# Cansat2019_3279_Container_v04.net
KiCad netlist of a schematic drawn in EAGLE
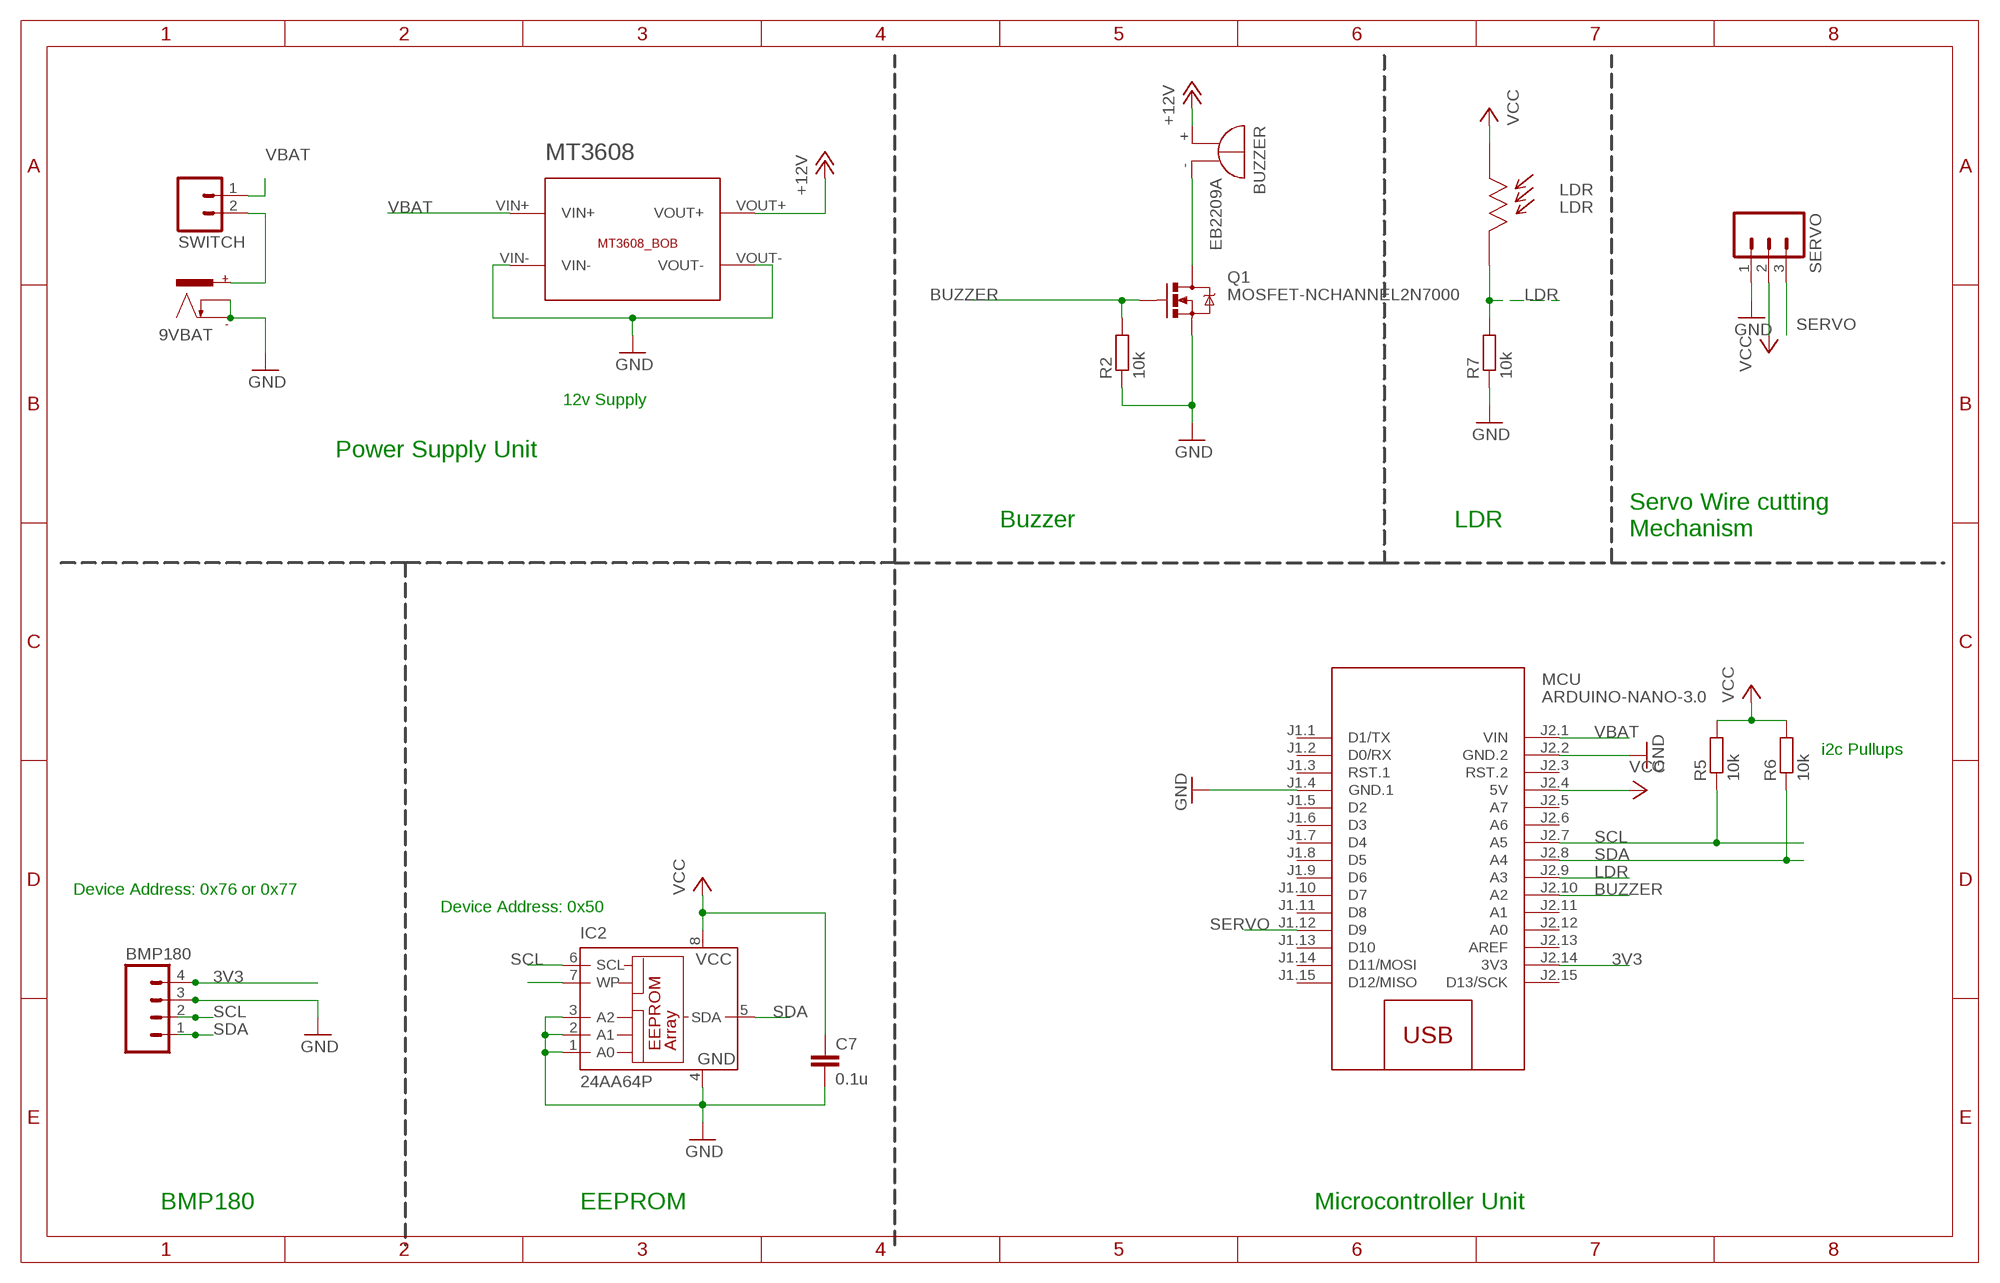
[diagram p0: schematic, sheet 1]

(export (version "E")
  (design (tool "Eeschema 10.0.6"))
  (components
    (comp (ref "9VBAT")
      (value "POWER_CON")
      (footprint "eagle-import:NEB21R")
      (libsource (lib "eagle-import") (part "POWER_CON"))
    )
    (comp (ref "BMP180")
      (value "M04")
      (footprint "eagle-import:04P")
      (libsource (lib "eagle-import") (part "M04"))
    )
    (comp (ref "BUZZER")
      (value "EB2209A")
      (footprint "eagle-import:EB2209A")
      (libsource (lib "eagle-import") (part "EB2209A"))
    )
    (comp (ref "C7")
      (value "0.1u")
      (footprint "eagle-import:C025-025X050")
      (libsource (lib "eagle-import") (part "C-EU025-025X050"))
    )
    (comp (ref "IC2")
      (value "24AA64P")
      (footprint "eagle-import:DIL8")
      (fields (field (name "MF") "MICROCHIP") (field (name "MPN") "24AA64-I/P"))
      (libsource (lib "eagle-import") (part "24PAA64"))
    )
    (comp (ref "LDR")
      (value "LDR")
      (footprint "eagle-import:LDR-5MM")
      (libsource (lib "eagle-import") (part "LDR"))
    )
    (comp (ref "MCU")
      (value "ARDUINO-NANO-3.0")
      (footprint "eagle-import:ARDUINO-NANO-3.0")
      (libsource (lib "eagle-import") (part "ARDUINO-NANO-3.0"))
    )
    (comp (ref "MT3608")
      (value "MT3608_BOB")
      (footprint "eagle-import:MT3608_BOB")
      (libsource (lib "eagle-import") (part "MT3608_BOB"))
    )
    (comp (ref "Q1")
      (value "MOSFET-NCHANNEL2N7000")
      (footprint "eagle-import:TO-92")
      (libsource (lib "eagle-import") (part "MOSFET-NCHANNEL2N7000"))
    )
    (comp (ref "R2")
      (value "10k")
      (footprint "eagle-import:0204_7")
      (libsource (lib "eagle-import") (part "R-EU_0204/7"))
    )
    (comp (ref "R5")
      (value "10k")
      (footprint "eagle-import:0204_7")
      (libsource (lib "eagle-import") (part "R-EU_0204/7"))
    )
    (comp (ref "R6")
      (value "10k")
      (footprint "eagle-import:0204_7")
      (libsource (lib "eagle-import") (part "R-EU_0204/7"))
    )
    (comp (ref "R7")
      (value "10k")
      (footprint "eagle-import:0204_7")
      (libsource (lib "eagle-import") (part "R-EU_0204/7"))
    )
    (comp (ref "SERVO")
      (value "M03")
      (footprint "eagle-import:03P")
      (libsource (lib "eagle-import") (part "M03"))
    )
    (comp (ref "SWITCH")
      (value "M02")
      (footprint "eagle-import:02P")
      (libsource (lib "eagle-import") (part "M02"))
    )
  )
  (nets
    (net (code "1") (name "+12V") (class "Default")
      (node (ref "BUZZER") (pin "+") (pinfunction "+_+") (pintype "passive"))
      (node (ref "MT3608") (pin "VOUT+") (pinfunction "VOUT+_VOUT+") (pintype "bidirectional"))
    )
    (net (code "2") (name "/3V3") (class "Default")
      (node (ref "BMP180") (pin "4") (pinfunction "4_4") (pintype "passive"))
      (node (ref "MCU") (pin "J2.14") (pinfunction "3V3_J2.14") (pintype "power_in"))
    )
    (net (code "3") (name "/BUZZER") (class "Default")
      (node (ref "MCU") (pin "J2.10") (pinfunction "A2_J2.10") (pintype "bidirectional"))
      (node (ref "Q1") (pin "2") (pinfunction "G_2") (pintype "passive"))
      (node (ref "R2") (pin "2") (pinfunction "2_2") (pintype "passive"))
    )
    (net (code "4") (name "/LDR") (class "Default")
      (node (ref "LDR") (pin "P$2") (pinfunction "P$2_P$2") (pintype "bidirectional"))
      (node (ref "MCU") (pin "J2.9") (pinfunction "A3_J2.9") (pintype "bidirectional"))
      (node (ref "R7") (pin "2") (pinfunction "2_2") (pintype "passive"))
    )
    (net (code "5") (name "/SCL") (class "Default")
      (node (ref "BMP180") (pin "2") (pinfunction "2_2") (pintype "passive"))
      (node (ref "IC2") (pin "6") (pinfunction "SCL_6") (pintype "input"))
      (node (ref "MCU") (pin "J2.7") (pinfunction "A5_J2.7") (pintype "bidirectional"))
      (node (ref "R5") (pin "1") (pinfunction "1_1") (pintype "passive"))
    )
    (net (code "6") (name "/SDA") (class "Default")
      (node (ref "BMP180") (pin "1") (pinfunction "1_1") (pintype "passive"))
      (node (ref "IC2") (pin "5") (pinfunction "SDA_5") (pintype "bidirectional"))
      (node (ref "MCU") (pin "J2.8") (pinfunction "A4_J2.8") (pintype "bidirectional"))
      (node (ref "R6") (pin "1") (pinfunction "1_1") (pintype "passive"))
    )
    (net (code "7") (name "/SERVO") (class "Default")
      (node (ref "MCU") (pin "J1.12") (pinfunction "D9_J1.12") (pintype "bidirectional"))
      (node (ref "SERVO") (pin "3") (pinfunction "3_3") (pintype "passive"))
    )
    (net (code "8") (name "/VBAT") (class "Default")
      (node (ref "MCU") (pin "J2.1") (pinfunction "VIN_J2.1") (pintype "power_in"))
      (node (ref "MT3608") (pin "VIN+") (pinfunction "VIN+_VIN+") (pintype "bidirectional"))
      (node (ref "SWITCH") (pin "1") (pinfunction "1_1") (pintype "passive"))
    )
    (net (code "9") (name "GND") (class "Default")
      (node (ref "9VBAT") (pin "-") (pinfunction "-_-") (pintype "passive"))
      (node (ref "9VBAT") (pin "C") (pinfunction "C_C") (pintype "passive"))
      (node (ref "BMP180") (pin "3") (pinfunction "3_3") (pintype "passive"))
      (node (ref "C7") (pin "2") (pinfunction "2_2") (pintype "passive"))
      (node (ref "IC2") (pin "1") (pinfunction "A0_1") (pintype "input"))
      (node (ref "IC2") (pin "2") (pinfunction "A1_2") (pintype "input"))
      (node (ref "IC2") (pin "3") (pinfunction "A2_3") (pintype "input"))
      (node (ref "IC2") (pin "4") (pinfunction "GND_4") (pintype "power_in"))
      (node (ref "MCU") (pin "J1.4") (pinfunction "GND.1_J1.4") (pintype "power_in"))
      (node (ref "MCU") (pin "J2.2") (pinfunction "GND.2_J2.2") (pintype "power_in"))
      (node (ref "MT3608") (pin "VIN-") (pinfunction "VIN-_VIN-") (pintype "bidirectional"))
      (node (ref "MT3608") (pin "VOUT-") (pinfunction "VOUT-_VOUT-") (pintype "bidirectional"))
      (node (ref "Q1") (pin "1") (pinfunction "S_1") (pintype "passive"))
      (node (ref "R2") (pin "1") (pinfunction "1_1") (pintype "passive"))
      (node (ref "R7") (pin "1") (pinfunction "1_1") (pintype "passive"))
      (node (ref "SERVO") (pin "1") (pinfunction "1_1") (pintype "passive"))
    )
    (net (code "10") (name "Net-(9VBAT-Pad+)") (class "Default")
      (node (ref "9VBAT") (pin "+") (pinfunction "+_+") (pintype "passive"))
      (node (ref "SWITCH") (pin "2") (pinfunction "2_2") (pintype "passive"))
    )
    (net (code "11") (name "Net-(Q1-D)") (class "Default")
      (node (ref "BUZZER") (pin "-") (pinfunction "-_-") (pintype "passive"))
      (node (ref "Q1") (pin "3") (pinfunction "D_3") (pintype "passive"))
    )
    (net (code "12") (name "VCC") (class "Default")
      (node (ref "C7") (pin "1") (pinfunction "1_1") (pintype "passive"))
      (node (ref "IC2") (pin "8") (pinfunction "VCC_8") (pintype "power_in"))
      (node (ref "LDR") (pin "P$1") (pinfunction "P$1_P$1") (pintype "bidirectional"))
      (node (ref "MCU") (pin "J2.4") (pinfunction "5V_J2.4") (pintype "power_in"))
      (node (ref "R5") (pin "2") (pinfunction "2_2") (pintype "passive"))
      (node (ref "R6") (pin "2") (pinfunction "2_2") (pintype "passive"))
      (node (ref "SERVO") (pin "2") (pinfunction "2_2") (pintype "passive"))
    )
    (net (code "13") (name "unconnected-(IC2-WP-Pad7)") (class "Default")
      (node (ref "IC2") (pin "7") (pinfunction "WP_7") (pintype "input"))
    )
    (net (code "14") (name "unconnected-(MCU-A0-PadJ2.12)") (class "Default")
      (node (ref "MCU") (pin "J2.12") (pinfunction "A0_J2.12") (pintype "bidirectional"))
    )
    (net (code "15") (name "unconnected-(MCU-A1-PadJ2.11)") (class "Default")
      (node (ref "MCU") (pin "J2.11") (pinfunction "A1_J2.11") (pintype "bidirectional"))
    )
    (net (code "16") (name "unconnected-(MCU-A6-PadJ2.6)") (class "Default")
      (node (ref "MCU") (pin "J2.6") (pinfunction "A6_J2.6") (pintype "bidirectional"))
    )
    (net (code "17") (name "unconnected-(MCU-A7-PadJ2.5)") (class "Default")
      (node (ref "MCU") (pin "J2.5") (pinfunction "A7_J2.5") (pintype "bidirectional"))
    )
    (net (code "18") (name "unconnected-(MCU-AREF-PadJ2.13)") (class "Default")
      (node (ref "MCU") (pin "J2.13") (pinfunction "AREF_J2.13") (pintype "bidirectional"))
    )
    (net (code "19") (name "unconnected-(MCU-D0{slash}RX-PadJ1.2)") (class "Default")
      (node (ref "MCU") (pin "J1.2") (pinfunction "D0/RX_J1.2") (pintype "bidirectional"))
    )
    (net (code "20") (name "unconnected-(MCU-D1{slash}TX-PadJ1.1)") (class "Default")
      (node (ref "MCU") (pin "J1.1") (pinfunction "D1/TX_J1.1") (pintype "bidirectional"))
    )
    (net (code "21") (name "unconnected-(MCU-D2-PadJ1.5)") (class "Default")
      (node (ref "MCU") (pin "J1.5") (pinfunction "D2_J1.5") (pintype "bidirectional"))
    )
    (net (code "22") (name "unconnected-(MCU-D3-PadJ1.6)") (class "Default")
      (node (ref "MCU") (pin "J1.6") (pinfunction "D3_J1.6") (pintype "bidirectional"))
    )
    (net (code "23") (name "unconnected-(MCU-D4-PadJ1.7)") (class "Default")
      (node (ref "MCU") (pin "J1.7") (pinfunction "D4_J1.7") (pintype "bidirectional"))
    )
    (net (code "24") (name "unconnected-(MCU-D5-PadJ1.8)") (class "Default")
      (node (ref "MCU") (pin "J1.8") (pinfunction "D5_J1.8") (pintype "bidirectional"))
    )
    (net (code "25") (name "unconnected-(MCU-D6-PadJ1.9)") (class "Default")
      (node (ref "MCU") (pin "J1.9") (pinfunction "D6_J1.9") (pintype "bidirectional"))
    )
    (net (code "26") (name "unconnected-(MCU-D7-PadJ1.10)") (class "Default")
      (node (ref "MCU") (pin "J1.10") (pinfunction "D7_J1.10") (pintype "bidirectional"))
    )
    (net (code "27") (name "unconnected-(MCU-D8-PadJ1.11)") (class "Default")
      (node (ref "MCU") (pin "J1.11") (pinfunction "D8_J1.11") (pintype "bidirectional"))
    )
    (net (code "28") (name "unconnected-(MCU-D10-PadJ1.13)") (class "Default")
      (node (ref "MCU") (pin "J1.13") (pinfunction "D10_J1.13") (pintype "bidirectional"))
    )
    (net (code "29") (name "unconnected-(MCU-D11{slash}MOSI-PadJ1.14)") (class "Default")
      (node (ref "MCU") (pin "J1.14") (pinfunction "D11/MOSI_J1.14") (pintype "bidirectional"))
    )
    (net (code "30") (name "unconnected-(MCU-D12{slash}MISO-PadJ1.15)") (class "Default")
      (node (ref "MCU") (pin "J1.15") (pinfunction "D12/MISO_J1.15") (pintype "bidirectional"))
    )
    (net (code "31") (name "unconnected-(MCU-D13{slash}SCK-PadJ2.15)") (class "Default")
      (node (ref "MCU") (pin "J2.15") (pinfunction "D13/SCK_J2.15") (pintype "bidirectional"))
    )
    (net (code "32") (name "unconnected-(MCU-RST.1-PadJ1.3)") (class "Default")
      (node (ref "MCU") (pin "J1.3") (pinfunction "RST.1_J1.3") (pintype "bidirectional"))
    )
    (net (code "33") (name "unconnected-(MCU-RST.2-PadJ2.3)") (class "Default")
      (node (ref "MCU") (pin "J2.3") (pinfunction "RST.2_J2.3") (pintype "bidirectional"))
    )
  )
)
